# ethernet-dlt.net
KiCad netlist of a schematic drawn in EAGLE
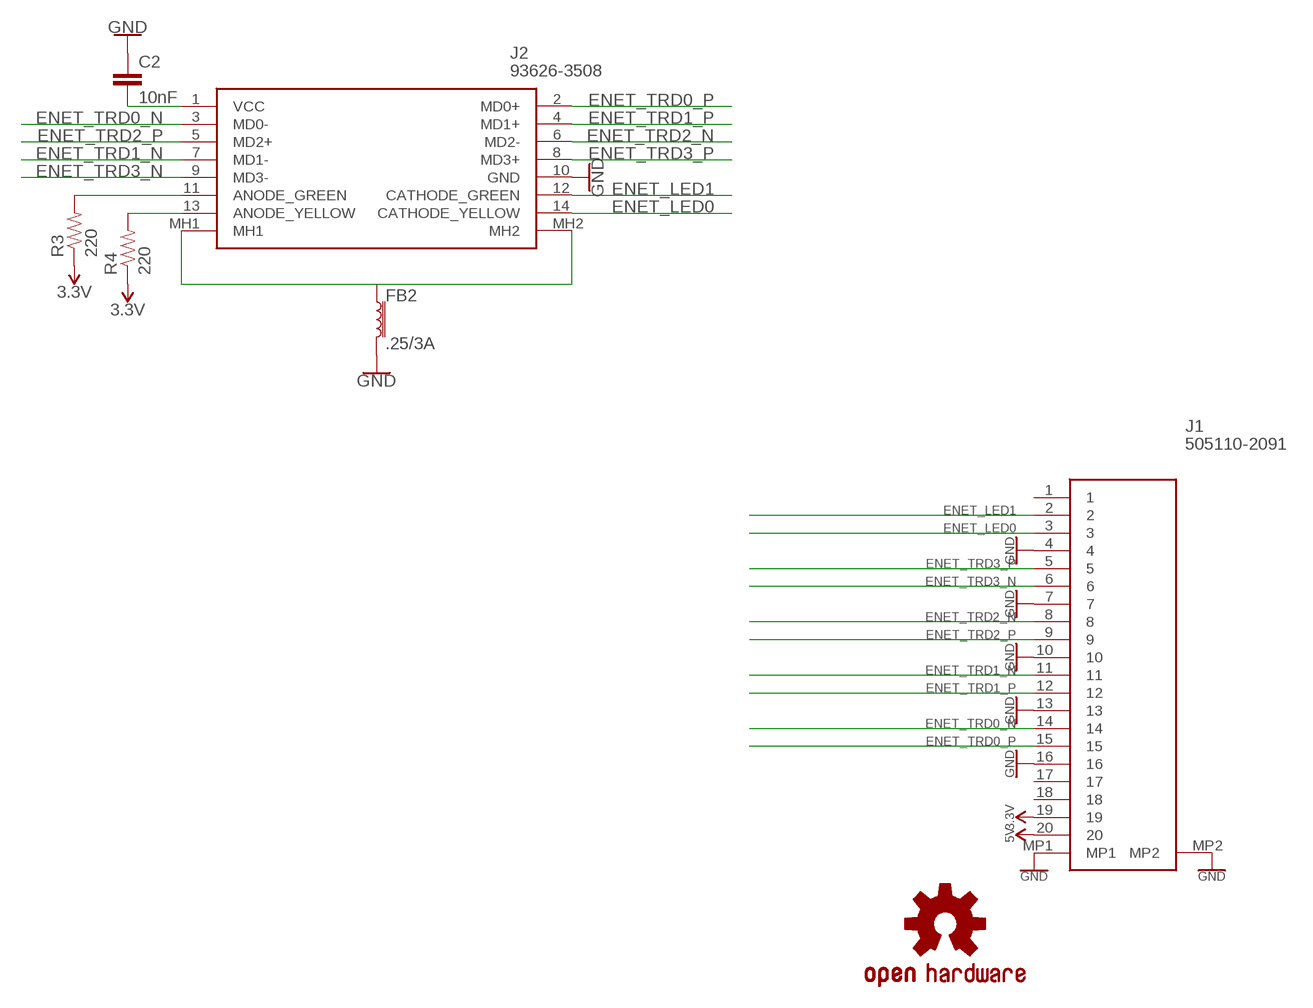
[diagram p0: schematic, sheet 1]

(export (version "E")
  (design (tool "Eeschema 10.0.6"))
  (components
    (comp (ref "C2")
      (value "10nF")
      (footprint "eagle-import:0603")
      (libsource (lib "eagle-import") (part "10NF-0603-50V-10%"))
    )
    (comp (ref "FB2")
      (value ".25/3A")
      (footprint "eagle-import:0603")
      (libsource (lib "eagle-import") (part "FERRITE_BEAD-0603"))
    )
    (comp (ref "J1")
      (value "505110-2091")
      (footprint "eagle-import:5051102091")
      (fields (field (name "MOUSER_PART_NUMBER") "538-505110-2091"))
      (libsource (lib "eagle-import") (part "505110-2091"))
    )
    (comp (ref "J2")
      (value "93626-3508")
      (footprint "eagle-import:936263508")
      (fields (field (name "MOUSER_PART_NUMBER") "538-93626-3508"))
      (libsource (lib "eagle-import") (part "93626-3508"))
    )
    (comp (ref "LOGO1")
      (value "OSHW-LOGOS-COPPER")
      (footprint "eagle-import:OSHW-LOGO-S_COPPER")
      (libsource (lib "eagle-import") (part "OSHW-LOGOS-COPPER"))
    )
    (comp (ref "R3")
      (value "220")
      (footprint "eagle-import:0805")
      (libsource (lib "eagle-import") (part "RESISTOR0805-RES"))
    )
    (comp (ref "R4")
      (value "220")
      (footprint "eagle-import:0805")
      (libsource (lib "eagle-import") (part "RESISTOR0805-RES"))
    )
  )
  (nets
    (net (code "1") (name "/ENET_LED0") (class "Default")
      (node (ref "J1") (pin "3") (pinfunction "3_3") (pintype "bidirectional"))
      (node (ref "J2") (pin "14") (pinfunction "CATHODE_YELLOW_14") (pintype "bidirectional"))
    )
    (net (code "2") (name "/ENET_LED1") (class "Default")
      (node (ref "J1") (pin "2") (pinfunction "2_2") (pintype "bidirectional"))
      (node (ref "J2") (pin "12") (pinfunction "CATHODE_GREEN_12") (pintype "bidirectional"))
    )
    (net (code "3") (name "/ENET_TRD0_N") (class "Default")
      (node (ref "J1") (pin "14") (pinfunction "14_14") (pintype "bidirectional"))
      (node (ref "J2") (pin "3") (pinfunction "MD0-_3") (pintype "bidirectional"))
    )
    (net (code "4") (name "/ENET_TRD0_P") (class "Default")
      (node (ref "J1") (pin "15") (pinfunction "15_15") (pintype "bidirectional"))
      (node (ref "J2") (pin "2") (pinfunction "MD0+_2") (pintype "bidirectional"))
    )
    (net (code "5") (name "/ENET_TRD1_N") (class "Default")
      (node (ref "J1") (pin "11") (pinfunction "11_11") (pintype "bidirectional"))
      (node (ref "J2") (pin "7") (pinfunction "MD1-_7") (pintype "bidirectional"))
    )
    (net (code "6") (name "/ENET_TRD1_P") (class "Default")
      (node (ref "J1") (pin "12") (pinfunction "12_12") (pintype "bidirectional"))
      (node (ref "J2") (pin "4") (pinfunction "MD1+_4") (pintype "bidirectional"))
    )
    (net (code "7") (name "/ENET_TRD2_N") (class "Default")
      (node (ref "J1") (pin "8") (pinfunction "8_8") (pintype "bidirectional"))
      (node (ref "J2") (pin "6") (pinfunction "MD2-_6") (pintype "bidirectional"))
    )
    (net (code "8") (name "/ENET_TRD2_P") (class "Default")
      (node (ref "J1") (pin "9") (pinfunction "9_9") (pintype "bidirectional"))
      (node (ref "J2") (pin "5") (pinfunction "MD2+_5") (pintype "bidirectional"))
    )
    (net (code "9") (name "/ENET_TRD3_N") (class "Default")
      (node (ref "J1") (pin "6") (pinfunction "6_6") (pintype "bidirectional"))
      (node (ref "J2") (pin "9") (pinfunction "MD3-_9") (pintype "bidirectional"))
    )
    (net (code "10") (name "/ENET_TRD3_P") (class "Default")
      (node (ref "J1") (pin "5") (pinfunction "5_5") (pintype "bidirectional"))
      (node (ref "J2") (pin "8") (pinfunction "MD3+_8") (pintype "bidirectional"))
    )
    (net (code "11") (name "3.3V") (class "Default")
      (node (ref "J1") (pin "19") (pinfunction "19_19") (pintype "bidirectional"))
      (node (ref "R3") (pin "1") (pinfunction "1_1") (pintype "passive"))
      (node (ref "R4") (pin "1") (pinfunction "1_1") (pintype "passive"))
    )
    (net (code "12") (name "5V") (class "Default")
      (node (ref "J1") (pin "20") (pinfunction "20_20") (pintype "bidirectional"))
    )
    (net (code "13") (name "GND") (class "Default")
      (node (ref "C2") (pin "1") (pinfunction "1_1") (pintype "passive"))
      (node (ref "FB2") (pin "2") (pinfunction "2_2") (pintype "passive"))
      (node (ref "J1") (pin "10") (pinfunction "10_10") (pintype "bidirectional"))
      (node (ref "J1") (pin "13") (pinfunction "13_13") (pintype "bidirectional"))
      (node (ref "J1") (pin "16") (pinfunction "16_16") (pintype "bidirectional"))
      (node (ref "J1") (pin "4") (pinfunction "4_4") (pintype "bidirectional"))
      (node (ref "J1") (pin "7") (pinfunction "7_7") (pintype "bidirectional"))
      (node (ref "J1") (pin "MP1") (pinfunction "MP1_MP1") (pintype "bidirectional"))
      (node (ref "J1") (pin "MP2") (pinfunction "MP2_MP2") (pintype "bidirectional"))
      (node (ref "J2") (pin "10") (pinfunction "GND_10") (pintype "bidirectional"))
    )
    (net (code "14") (name "Net-(FB2-Pad1)") (class "Default")
      (node (ref "FB2") (pin "1") (pinfunction "1_1") (pintype "passive"))
      (node (ref "J2") (pin "MH1") (pinfunction "MH1_MH1") (pintype "bidirectional"))
      (node (ref "J2") (pin "MH2") (pinfunction "MH2_MH2") (pintype "bidirectional"))
    )
    (net (code "15") (name "Net-(J2-ANODE_GREEN)") (class "Default")
      (node (ref "J2") (pin "11") (pinfunction "ANODE_GREEN_11") (pintype "bidirectional"))
      (node (ref "R3") (pin "2") (pinfunction "2_2") (pintype "passive"))
    )
    (net (code "16") (name "Net-(J2-ANODE_YELLOW)") (class "Default")
      (node (ref "J2") (pin "13") (pinfunction "ANODE_YELLOW_13") (pintype "bidirectional"))
      (node (ref "R4") (pin "2") (pinfunction "2_2") (pintype "passive"))
    )
    (net (code "17") (name "Net-(J2-VCC)") (class "Default")
      (node (ref "C2") (pin "2") (pinfunction "2_2") (pintype "passive"))
      (node (ref "J2") (pin "1") (pinfunction "VCC_1") (pintype "bidirectional"))
    )
    (net (code "18") (name "unconnected-(J1-Pad1)") (class "Default")
      (node (ref "J1") (pin "1") (pinfunction "1_1") (pintype "bidirectional"))
    )
    (net (code "19") (name "unconnected-(J1-Pad17)") (class "Default")
      (node (ref "J1") (pin "17") (pinfunction "17_17") (pintype "bidirectional"))
    )
    (net (code "20") (name "unconnected-(J1-Pad18)") (class "Default")
      (node (ref "J1") (pin "18") (pinfunction "18_18") (pintype "bidirectional"))
    )
  )
)
